# Power.net
KiCad netlist of a schematic drawn in Altium Designer
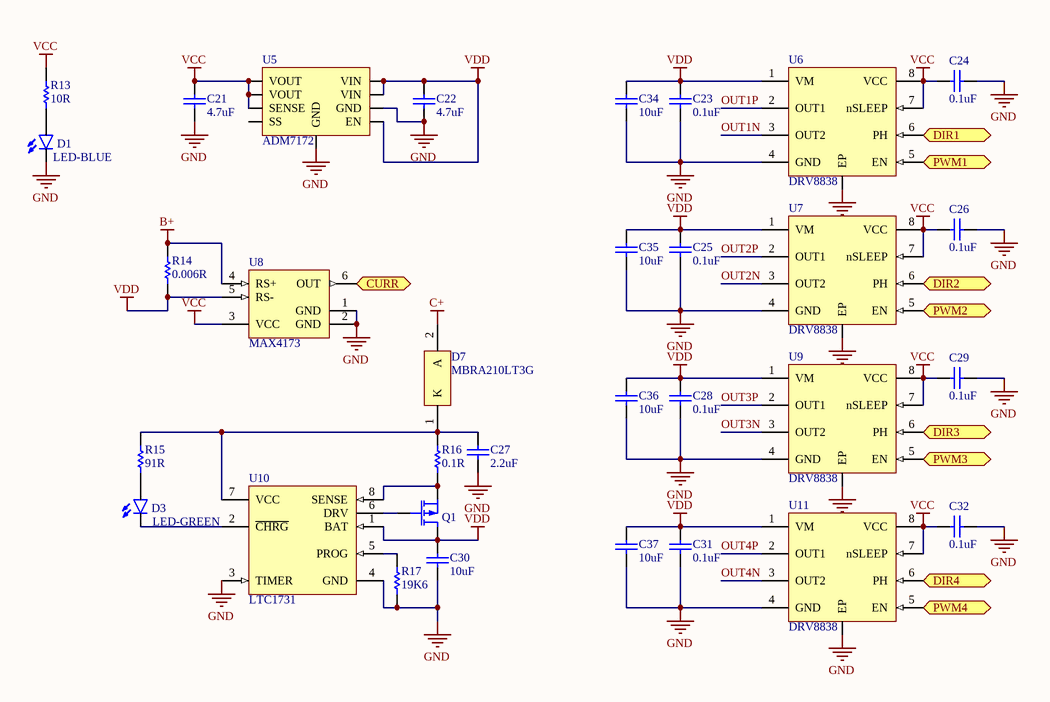
[diagram p0: Power.SchDoc]

(export (version "E")
  (design (tool "Eeschema 10.0.6"))
  (components
    (comp (ref "C21")
      (value "4.7uF")
      (footprint "CAPC0402(1005)60_L")
      (description "CAP 4.7uF 6.3V ±10% 0402 (1005 Metric) Thickness 0.6mm SMD")
      (fields (field (name "TOLERANCE") "Â±10%"))
      (libsource (lib "Altium Content Vault") (part "CAP"))
    )
    (comp (ref "C22")
      (value "4.7uF")
      (footprint "CAPC0402(1005)60_L")
      (description "CAP 4.7uF 6.3V ±10% 0402 (1005 Metric) Thickness 0.6mm SMD")
      (fields (field (name "TOLERANCE") "Â±10%"))
      (libsource (lib "Altium Content Vault") (part "CAP"))
    )
    (comp (ref "C23")
      (value "0.1uF")
      (footprint "CAPC0402(1005)60_L")
      (description "CAP 4.7uF 6.3V ±10% 0402 (1005 Metric) Thickness 0.6mm SMD")
      (fields (field (name "TOLERANCE") "Â±10%"))
      (libsource (lib "Altium Content Vault") (part "CMP-1034-02136-1"))
    )
    (comp (ref "C24")
      (value "0.1uF")
      (footprint "CAPC0402(1005)60_L")
      (description "CAP 4.7uF 6.3V ±10% 0402 (1005 Metric) Thickness 0.6mm SMD")
      (fields (field (name "TOLERANCE") "Â±10%"))
      (libsource (lib "Altium Content Vault") (part "CMP-1034-02136-1"))
    )
    (comp (ref "C25")
      (value "0.1uF")
      (footprint "CAPC0402(1005)60_L")
      (description "CAP 4.7uF 6.3V ±10% 0402 (1005 Metric) Thickness 0.6mm SMD")
      (fields (field (name "TOLERANCE") "Â±10%"))
      (libsource (lib "Altium Content Vault") (part "CMP-1034-02136-1"))
    )
    (comp (ref "C26")
      (value "0.1uF")
      (footprint "CAPC0402(1005)60_L")
      (description "CAP 4.7uF 6.3V ±10% 0402 (1005 Metric) Thickness 0.6mm SMD")
      (fields (field (name "TOLERANCE") "Â±10%"))
      (libsource (lib "Altium Content Vault") (part "CMP-1034-02136-1"))
    )
    (comp (ref "C27")
      (value "2.2uF")
      (footprint "CAPC0402(1005)60_M")
      (description "CAP 2.2uF 6.3V ±10% 0402 (1005 Metric) Thickness 0.6mm SMD")
      (fields (field (name "TOLERANCE") "Â±10%"))
      (libsource (lib "Altium Content Vault") (part "CAP"))
    )
    (comp (ref "C28")
      (value "0.1uF")
      (footprint "CAPC0402(1005)60_L")
      (description "CAP 4.7uF 6.3V ±10% 0402 (1005 Metric) Thickness 0.6mm SMD")
      (fields (field (name "TOLERANCE") "Â±10%"))
      (libsource (lib "Altium Content Vault") (part "CMP-1034-02136-1"))
    )
    (comp (ref "C29")
      (value "0.1uF")
      (footprint "CAPC0402(1005)60_L")
      (description "CAP 4.7uF 6.3V ±10% 0402 (1005 Metric) Thickness 0.6mm SMD")
      (fields (field (name "TOLERANCE") "Â±10%"))
      (libsource (lib "Altium Content Vault") (part "CMP-1034-02136-1"))
    )
    (comp (ref "C30")
      (value "10uF")
      (footprint "CAPC0402(1005)60_N")
      (description "CAP 10uF 6.3V ±20% 0402 (1005 Metric) Thickness 0.6mm SMD")
      (fields (field (name "TOLERANCE") "Â±20%"))
      (libsource (lib "Altium Content Vault") (part "CAP"))
    )
    (comp (ref "C31")
      (value "0.1uF")
      (footprint "CAPC0402(1005)60_L")
      (description "CAP 4.7uF 6.3V ±10% 0402 (1005 Metric) Thickness 0.6mm SMD")
      (fields (field (name "TOLERANCE") "Â±10%"))
      (libsource (lib "Altium Content Vault") (part "CMP-1034-02136-1"))
    )
    (comp (ref "C32")
      (value "0.1uF")
      (footprint "CAPC0402(1005)60_L")
      (description "CAP 4.7uF 6.3V ±10% 0402 (1005 Metric) Thickness 0.6mm SMD")
      (fields (field (name "TOLERANCE") "Â±10%"))
      (libsource (lib "Altium Content Vault") (part "CMP-1034-02136-1"))
    )
    (comp (ref "C34")
      (value "10uF")
      (footprint "CAPC0603(1608)100_L")
      (description "CAP 10uF 6.3V ±10% 0603 (1608 Metric) Thickness 1mm SMD")
      (fields (field (name "TOLERANCE") "Â±10%"))
      (libsource (lib "Altium Content Vault") (part "CAP"))
    )
    (comp (ref "C35")
      (value "10uF")
      (footprint "CAPC0603(1608)100_L")
      (description "CAP 10uF 6.3V ±10% 0603 (1608 Metric) Thickness 1mm SMD")
      (fields (field (name "TOLERANCE") "Â±10%"))
      (libsource (lib "Altium Content Vault") (part "CAP"))
    )
    (comp (ref "C36")
      (value "10uF")
      (footprint "CAPC0603(1608)100_L")
      (description "CAP 10uF 6.3V ±10% 0603 (1608 Metric) Thickness 1mm SMD")
      (fields (field (name "TOLERANCE") "Â±10%"))
      (libsource (lib "Altium Content Vault") (part "CAP"))
    )
    (comp (ref "C37")
      (value "10uF")
      (footprint "CAPC0603(1608)100_L")
      (description "CAP 10uF 6.3V ±10% 0603 (1608 Metric) Thickness 1mm SMD")
      (fields (field (name "TOLERANCE") "Â±10%"))
      (libsource (lib "Altium Content Vault") (part "CAP"))
    )
    (comp (ref "D1")
      (value "LED-BLUE")
      (footprint "LED-1206")
      (libsource (lib "Components") (part "LED-BLUE1206"))
    )
    (comp (ref "D3")
      (value "LED-GREEN")
      (footprint "LED-1206")
      (libsource (lib "Components") (part "LED-GREEN1206"))
    )
    (comp (ref "D7")
      (value "MBRA210LT3G")
      (footprint "ONSC-SMA-2-403D-02_F_V")
      (description "Schottky Power Rectifier, 2-Pin SMA, Pb-Free, Tape and Reel")
      (fields (field (name "MANUFACTURER") "On Semiconductor"))
      (libsource (lib "Altium Content Vault") (part "ONSC-D-K1A2-2_A"))
    )
    (comp (ref "Q1")
      (value "MOSFET-P")
      (footprint "SOT23-3")
      (description "P-Channel MOSFET")
      (fields (field (name "PUBLISHER") "Altium Limited"))
      (libsource (lib "Components") (part "MOSFET-P"))
    )
    (comp (ref "R13")
      (value "10R")
      (footprint "RESC0402(1005)_N")
      (description "10R 0.063W 5% 0402 (1005 Metric)  SMD")
      (fields (field (name "POWER") "0.063 W") (field (name "TOLERANCE") "5 %"))
      (libsource (lib "Altium Content Vault") (part "RES"))
    )
    (comp (ref "R14")
      (value "0.006R")
      (footprint "RESC0805(2012)_N")
      (description "Jumper 0805 (2012 Metric)")
      (fields (field (name "TOLERANCE") "None"))
      (libsource (lib "Altium Content Vault") (part "RES"))
    )
    (comp (ref "R15")
      (value "91R")
      (footprint "RESC0402(1005)_M")
      (description "91R 0.063W 5% 0402 (1005 Metric)  SMD")
      (fields (field (name "POWER") "0.063 W") (field (name "TOLERANCE") "5 %"))
      (libsource (lib "Altium Content Vault") (part "RES"))
    )
    (comp (ref "R16")
      (value "0.1R")
      (footprint "RESC0603(1608)_M")
      (description "1R 0.1W 5% 0603 (1608 Metric)  SMD")
      (fields (field (name "POWER") "0.1 W") (field (name "TOLERANCE") "5 %"))
      (libsource (lib "Altium Content Vault") (part "RES"))
    )
    (comp (ref "R17")
      (value "19K6")
      (footprint "RESC0402(1005)_M")
      (description "20K 0.063W 5% 0402 (1005 Metric)  SMD")
      (fields (field (name "TOLERANCE") "5 %") (field (name "POWER") "0.063 W"))
      (libsource (lib "Altium Content Vault") (part "CMP-1011-00105-1"))
    )
    (comp (ref "U5")
      (value "ADM7172")
      (footprint "SON50P300X85_HS-9N")
      (libsource (lib "Components") (part "ADM7171"))
    )
    (comp (ref "U6")
      (value "DRV8838")
      (footprint "SON50P200X80_HS-9N")
      (fields (field (name "PARTNUMBER") "MTD6501G-HC1") (field (name "MANUFACTURER") "Microchip"))
      (libsource (lib "Components") (part "DRV8838"))
    )
    (comp (ref "U7")
      (value "DRV8838")
      (footprint "SON50P200X80_HS-9N")
      (fields (field (name "PARTNUMBER") "MTD6501G-HC1") (field (name "MANUFACTURER") "Microchip"))
      (libsource (lib "Components") (part "DRV8838"))
    )
    (comp (ref "U8")
      (value "MAX4173")
      (footprint "MAXM-U6+1_M")
      (fields (field (name "PARTNUMBER") "MAX4173FEUT+T"))
      (libsource (lib "Altium Content Vault") (part "CMP-0252-00331-1"))
    )
    (comp (ref "U9")
      (value "DRV8838")
      (footprint "SON50P200X80_HS-9N")
      (fields (field (name "PARTNUMBER") "MTD6501G-HC1") (field (name "MANUFACTURER") "Microchip"))
      (libsource (lib "Components") (part "DRV8838"))
    )
    (comp (ref "U10")
      (value "LTC1731")
      (footprint "LT-MS8-8_L")
      (fields
        (field (name "PARTNUMBER") "LTC1731EMS8-4.2#TRPBF")
        (field (name "MANUFACTURER") "Linear Technology")
      )
      (libsource (lib "Altium Content Vault") (part "LT-LTC1731-4_1_4_2-8"))
    )
    (comp (ref "U11")
      (value "DRV8838")
      (footprint "SON50P200X80_HS-9N")
      (fields (field (name "PARTNUMBER") "MTD6501G-HC1") (field (name "MANUFACTURER") "Microchip"))
      (libsource (lib "Components") (part "DRV8838"))
    )
  )
  (nets
    (net (code "1") (name "/CURR") (class "Default")
      (node (ref "U8") (pin "6") (pinfunction "OUT_6") (pintype "output"))
    )
    (net (code "2") (name "/DIR1") (class "Default")
      (node (ref "U6") (pin "6") (pinfunction "PH_6") (pintype "input"))
    )
    (net (code "3") (name "/DIR2") (class "Default")
      (node (ref "U7") (pin "6") (pinfunction "PH_6") (pintype "input"))
    )
    (net (code "4") (name "/DIR3") (class "Default")
      (node (ref "U9") (pin "6") (pinfunction "PH_6") (pintype "input"))
    )
    (net (code "5") (name "/DIR4") (class "Default")
      (node (ref "U11") (pin "6") (pinfunction "PH_6") (pintype "input"))
    )
    (net (code "6") (name "/OUT1N") (class "Default")
      (node (ref "U6") (pin "3") (pinfunction "OUT2_3") (pintype "tri_state"))
    )
    (net (code "7") (name "/OUT1P") (class "Default")
      (node (ref "U6") (pin "2") (pinfunction "OUT1_2") (pintype "tri_state"))
    )
    (net (code "8") (name "/OUT2N") (class "Default")
      (node (ref "U7") (pin "3") (pinfunction "OUT2_3") (pintype "tri_state"))
    )
    (net (code "9") (name "/OUT2P") (class "Default")
      (node (ref "U7") (pin "2") (pinfunction "OUT1_2") (pintype "tri_state"))
    )
    (net (code "10") (name "/OUT3N") (class "Default")
      (node (ref "U9") (pin "3") (pinfunction "OUT2_3") (pintype "tri_state"))
    )
    (net (code "11") (name "/OUT3P") (class "Default")
      (node (ref "U9") (pin "2") (pinfunction "OUT1_2") (pintype "tri_state"))
    )
    (net (code "12") (name "/OUT4N") (class "Default")
      (node (ref "U11") (pin "3") (pinfunction "OUT2_3") (pintype "tri_state"))
    )
    (net (code "13") (name "/OUT4P") (class "Default")
      (node (ref "U11") (pin "2") (pinfunction "OUT1_2") (pintype "tri_state"))
    )
    (net (code "14") (name "/PWM1") (class "Default")
      (node (ref "U6") (pin "5") (pinfunction "EN_5") (pintype "input"))
    )
    (net (code "15") (name "/PWM2") (class "Default")
      (node (ref "U7") (pin "5") (pinfunction "EN_5") (pintype "input"))
    )
    (net (code "16") (name "/PWM3") (class "Default")
      (node (ref "U9") (pin "5") (pinfunction "EN_5") (pintype "input"))
    )
    (net (code "17") (name "/PWM4") (class "Default")
      (node (ref "U11") (pin "5") (pinfunction "EN_5") (pintype "input"))
    )
    (net (code "18") (name "B+") (class "Default")
      (node (ref "R14") (pin "2") (pinfunction "2_2") (pintype "passive"))
      (node (ref "U8") (pin "4") (pinfunction "RS+_4") (pintype "input"))
    )
    (net (code "19") (name "C+") (class "Default")
      (node (ref "D7") (pin "2") (pinfunction "A_2") (pintype "passive"))
    )
    (net (code "20") (name "GND") (class "Default")
      (node (ref "C21") (pin "1") (pinfunction "1_1") (pintype "passive"))
      (node (ref "C22") (pin "1") (pinfunction "1_1") (pintype "passive"))
      (node (ref "C23") (pin "1") (pinfunction "1_1") (pintype "passive"))
      (node (ref "C24") (pin "2") (pinfunction "2_2") (pintype "passive"))
      (node (ref "C25") (pin "1") (pinfunction "1_1") (pintype "passive"))
      (node (ref "C26") (pin "2") (pinfunction "2_2") (pintype "passive"))
      (node (ref "C27") (pin "1") (pinfunction "1_1") (pintype "passive"))
      (node (ref "C28") (pin "1") (pinfunction "1_1") (pintype "passive"))
      (node (ref "C29") (pin "2") (pinfunction "2_2") (pintype "passive"))
      (node (ref "C30") (pin "1") (pinfunction "1_1") (pintype "passive"))
      (node (ref "C31") (pin "1") (pinfunction "1_1") (pintype "passive"))
      (node (ref "C32") (pin "2") (pinfunction "2_2") (pintype "passive"))
      (node (ref "C34") (pin "1") (pinfunction "1_1") (pintype "passive"))
      (node (ref "C35") (pin "1") (pinfunction "1_1") (pintype "passive"))
      (node (ref "C36") (pin "1") (pinfunction "1_1") (pintype "passive"))
      (node (ref "C37") (pin "1") (pinfunction "1_1") (pintype "passive"))
      (node (ref "D1") (pin "C") (pinfunction "C_C") (pintype "passive"))
      (node (ref "R17") (pin "1") (pinfunction "1_1") (pintype "passive"))
      (node (ref "U10") (pin "3") (pinfunction "TIMER_3") (pintype "input"))
      (node (ref "U10") (pin "4") (pinfunction "GND_4") (pintype "power_in"))
      (node (ref "U11") (pin "4") (pinfunction "GND_4") (pintype "power_in"))
      (node (ref "U11") (pin "9") (pinfunction "EP_9") (pintype "passive"))
      (node (ref "U5") (pin "6") (pinfunction "GND_6") (pintype "passive"))
      (node (ref "U5") (pin "9") (pinfunction "GND_9") (pintype "passive"))
      (node (ref "U6") (pin "4") (pinfunction "GND_4") (pintype "power_in"))
      (node (ref "U6") (pin "9") (pinfunction "EP_9") (pintype "passive"))
      (node (ref "U7") (pin "4") (pinfunction "GND_4") (pintype "power_in"))
      (node (ref "U7") (pin "9") (pinfunction "EP_9") (pintype "passive"))
      (node (ref "U8") (pin "1") (pinfunction "GND_1") (pintype "power_in"))
      (node (ref "U8") (pin "2") (pinfunction "GND_2") (pintype "power_in"))
      (node (ref "U9") (pin "4") (pinfunction "GND_4") (pintype "power_in"))
      (node (ref "U9") (pin "9") (pinfunction "EP_9") (pintype "passive"))
    )
    (net (code "21") (name "Net-(D1-PadA)") (class "Default")
      (node (ref "D1") (pin "A") (pinfunction "A_A") (pintype "passive"))
      (node (ref "R13") (pin "1") (pinfunction "1_1") (pintype "passive"))
    )
    (net (code "22") (name "Net-(D3-PadA)") (class "Default")
      (node (ref "D3") (pin "A") (pinfunction "A_A") (pintype "passive"))
      (node (ref "R15") (pin "1") (pinfunction "1_1") (pintype "passive"))
    )
    (net (code "23") (name "Net-(D7-K)") (class "Default")
      (node (ref "C27") (pin "2") (pinfunction "2_2") (pintype "passive"))
      (node (ref "D7") (pin "1") (pinfunction "K_1") (pintype "passive"))
      (node (ref "R15") (pin "2") (pinfunction "2_2") (pintype "passive"))
      (node (ref "R16") (pin "2") (pinfunction "2_2") (pintype "passive"))
      (node (ref "U10") (pin "7") (pinfunction "VCC_7") (pintype "power_in"))
    )
    (net (code "24") (name "Net-(Q1-G)") (class "Default")
      (node (ref "Q1") (pin "1") (pinfunction "G_1") (pintype "passive"))
      (node (ref "U10") (pin "6") (pinfunction "DRV_6") (pintype "tri_state"))
    )
    (net (code "25") (name "Net-(Q1-S)") (class "Default")
      (node (ref "Q1") (pin "3") (pinfunction "S_3") (pintype "passive"))
      (node (ref "R16") (pin "1") (pinfunction "1_1") (pintype "passive"))
      (node (ref "U10") (pin "8") (pinfunction "SENSE_8") (pintype "input"))
    )
    (net (code "26") (name "Net-(U10-PROG)") (class "Default")
      (node (ref "R17") (pin "2") (pinfunction "2_2") (pintype "passive"))
      (node (ref "U10") (pin "5") (pinfunction "PROG_5") (pintype "input"))
    )
    (net (code "27") (name "Net-(U10-~{CHRG})") (class "Default")
      (node (ref "D3") (pin "C") (pinfunction "C_C") (pintype "passive"))
      (node (ref "U10") (pin "2") (pinfunction "~{CHRG}_2") (pintype "tri_state"))
    )
    (net (code "28") (name "VCC") (class "Default")
      (node (ref "C21") (pin "2") (pinfunction "2_2") (pintype "passive"))
      (node (ref "C24") (pin "1") (pinfunction "1_1") (pintype "passive"))
      (node (ref "C26") (pin "1") (pinfunction "1_1") (pintype "passive"))
      (node (ref "C29") (pin "1") (pinfunction "1_1") (pintype "passive"))
      (node (ref "C32") (pin "1") (pinfunction "1_1") (pintype "passive"))
      (node (ref "R13") (pin "2") (pinfunction "2_2") (pintype "passive"))
      (node (ref "U11") (pin "7") (pinfunction "nSLEEP_7") (pintype "input"))
      (node (ref "U11") (pin "8") (pinfunction "VCC_8") (pintype "power_in"))
      (node (ref "U5") (pin "1") (pinfunction "VOUT_1") (pintype "passive"))
      (node (ref "U5") (pin "2") (pinfunction "VOUT_2") (pintype "passive"))
      (node (ref "U5") (pin "3") (pinfunction "SENSE_3") (pintype "passive"))
      (node (ref "U6") (pin "7") (pinfunction "nSLEEP_7") (pintype "input"))
      (node (ref "U6") (pin "8") (pinfunction "VCC_8") (pintype "power_in"))
      (node (ref "U7") (pin "7") (pinfunction "nSLEEP_7") (pintype "input"))
      (node (ref "U7") (pin "8") (pinfunction "VCC_8") (pintype "power_in"))
      (node (ref "U8") (pin "3") (pinfunction "VCC_3") (pintype "power_in"))
      (node (ref "U9") (pin "7") (pinfunction "nSLEEP_7") (pintype "input"))
      (node (ref "U9") (pin "8") (pinfunction "VCC_8") (pintype "power_in"))
    )
    (net (code "29") (name "VDD") (class "Default")
      (node (ref "C22") (pin "2") (pinfunction "2_2") (pintype "passive"))
      (node (ref "C23") (pin "2") (pinfunction "2_2") (pintype "passive"))
      (node (ref "C25") (pin "2") (pinfunction "2_2") (pintype "passive"))
      (node (ref "C28") (pin "2") (pinfunction "2_2") (pintype "passive"))
      (node (ref "C30") (pin "2") (pinfunction "2_2") (pintype "passive"))
      (node (ref "C31") (pin "2") (pinfunction "2_2") (pintype "passive"))
      (node (ref "C34") (pin "2") (pinfunction "2_2") (pintype "passive"))
      (node (ref "C35") (pin "2") (pinfunction "2_2") (pintype "passive"))
      (node (ref "C36") (pin "2") (pinfunction "2_2") (pintype "passive"))
      (node (ref "C37") (pin "2") (pinfunction "2_2") (pintype "passive"))
      (node (ref "Q1") (pin "2") (pinfunction "D_2") (pintype "passive"))
      (node (ref "R14") (pin "1") (pinfunction "1_1") (pintype "passive"))
      (node (ref "U10") (pin "1") (pinfunction "BAT_1") (pintype "input"))
      (node (ref "U11") (pin "1") (pinfunction "VM_1") (pintype "power_in"))
      (node (ref "U5") (pin "5") (pinfunction "EN_5") (pintype "passive"))
      (node (ref "U5") (pin "7") (pinfunction "VIN_7") (pintype "passive"))
      (node (ref "U5") (pin "8") (pinfunction "VIN_8") (pintype "passive"))
      (node (ref "U6") (pin "1") (pinfunction "VM_1") (pintype "power_in"))
      (node (ref "U7") (pin "1") (pinfunction "VM_1") (pintype "power_in"))
      (node (ref "U8") (pin "5") (pinfunction "RS-_5") (pintype "input"))
      (node (ref "U9") (pin "1") (pinfunction "VM_1") (pintype "power_in"))
    )
    (net (code "30") (name "unconnected-(U5-SS-Pad4)") (class "Default")
      (node (ref "U5") (pin "4") (pinfunction "SS_4") (pintype "passive"))
    )
  )
)
